# Display.net
KiCad netlist of a schematic drawn in Altium Designer
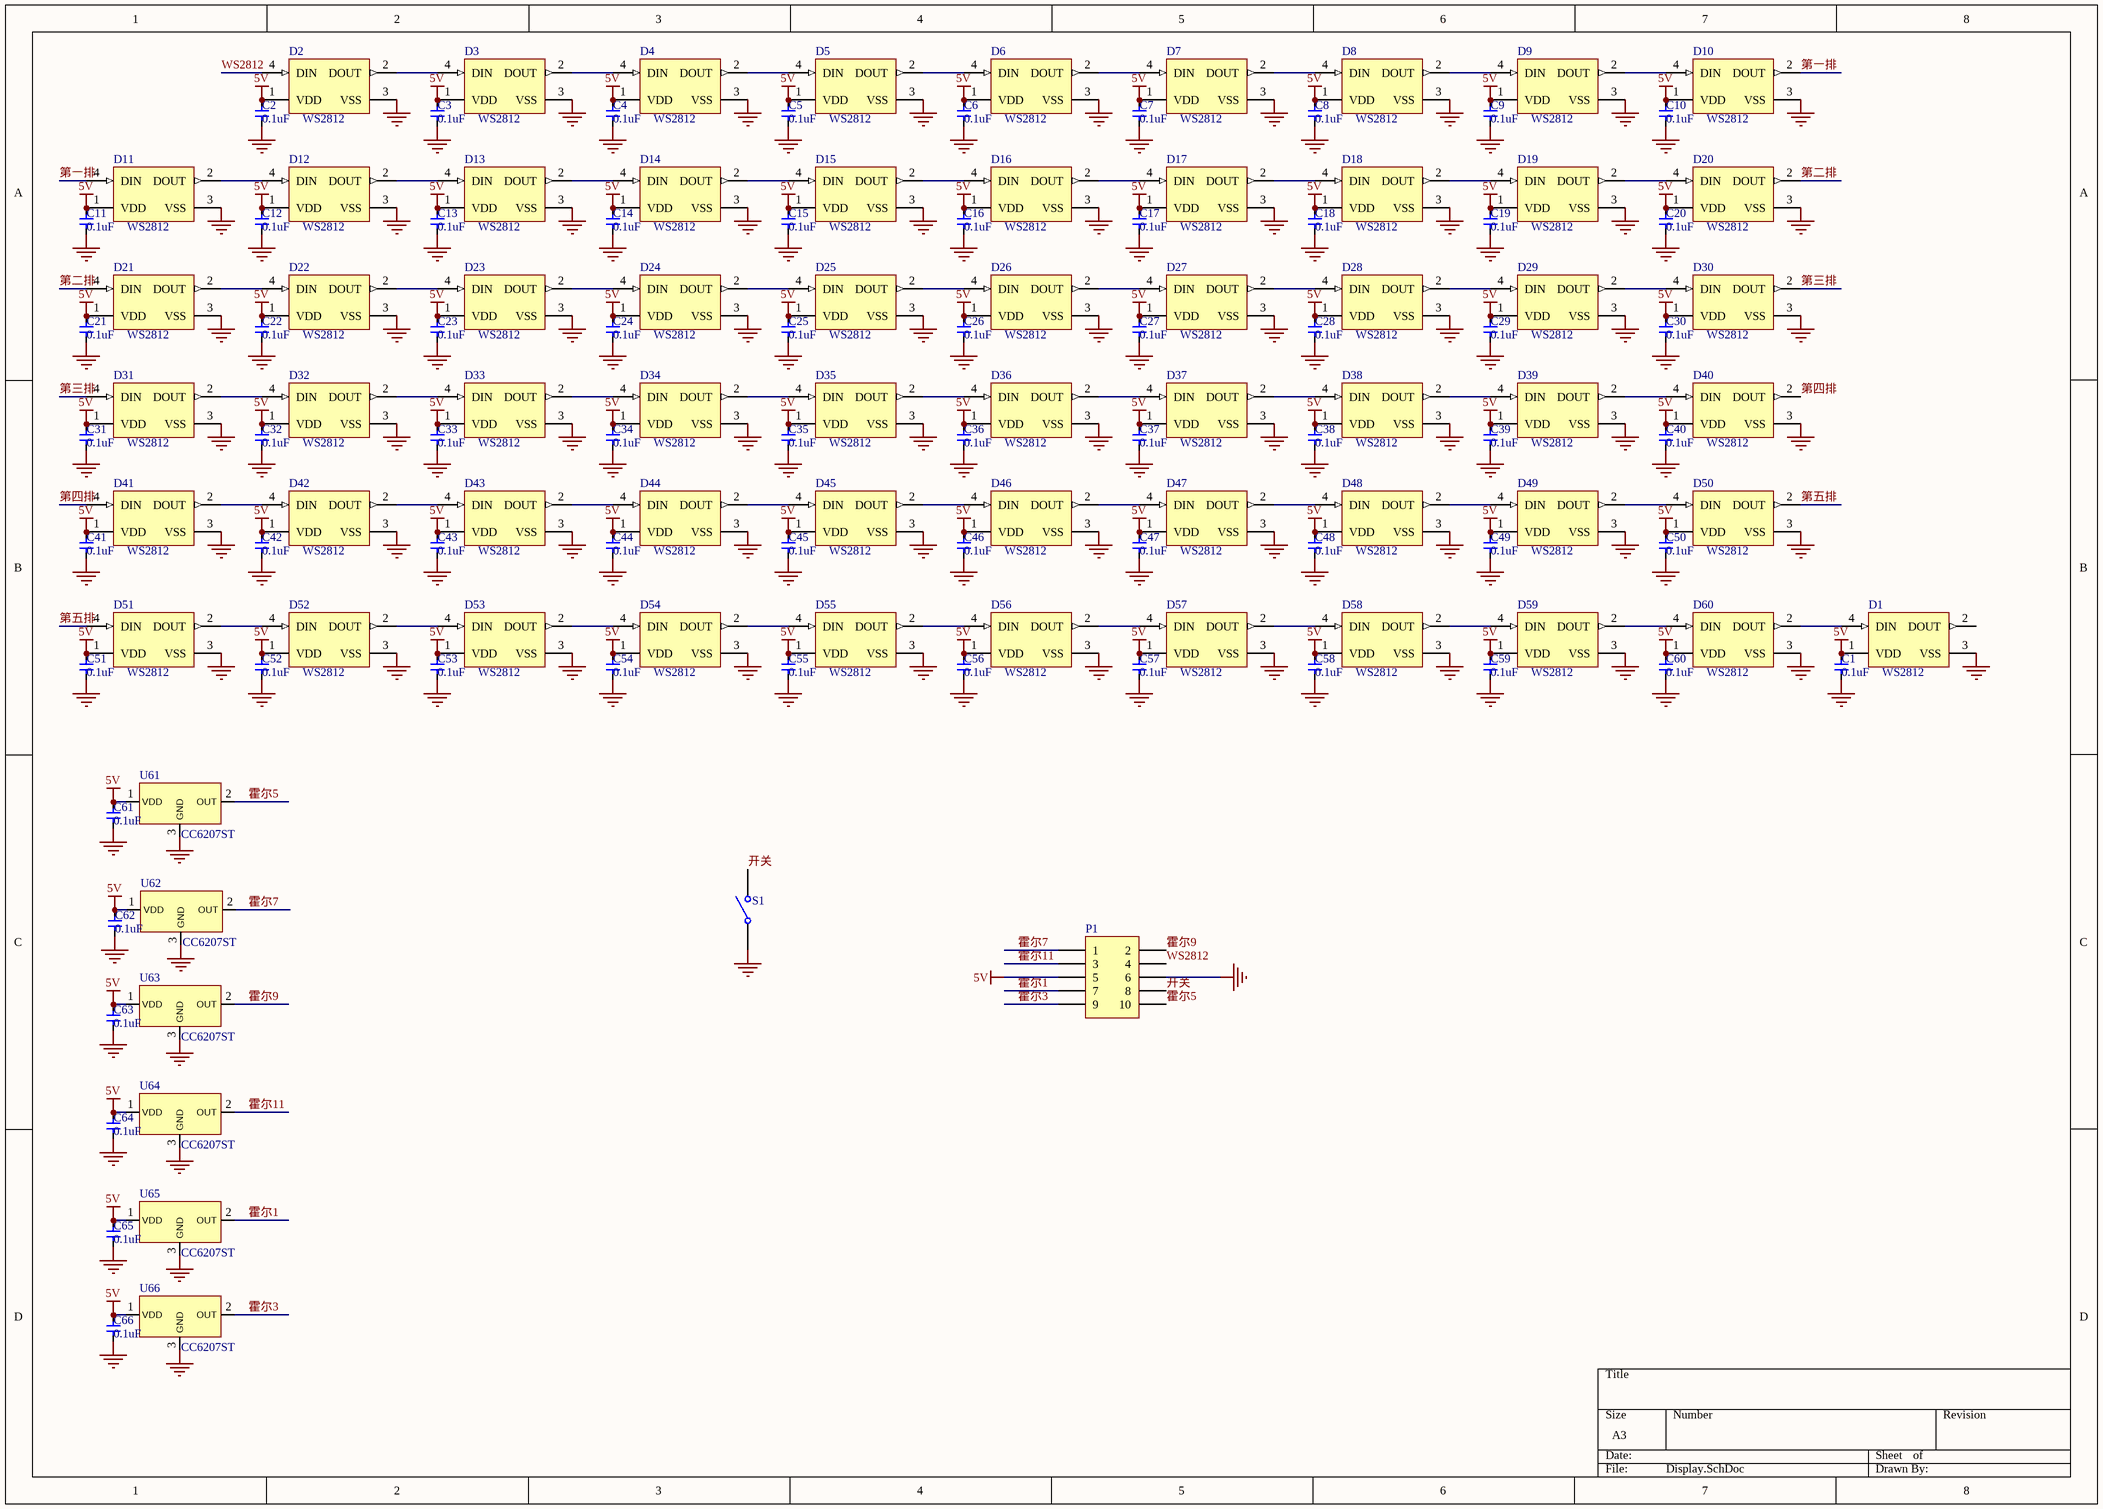
[diagram p0: Display.SchDoc]

(export (version "E")
  (design (tool "Eeschema 10.0.6"))
  (components
    (comp (ref "C1")
      (value "0.1uF")
      (footprint "0603_C")
      (description "Capacitor")
      (libsource (lib "MyPcbLib") (part "电容-0402"))
    )
    (comp (ref "C2")
      (value "0.1uF")
      (footprint "0603_C")
      (description "Capacitor")
      (libsource (lib "MyPcbLib") (part "电容-0402"))
    )
    (comp (ref "C3")
      (value "0.1uF")
      (footprint "0603_C")
      (description "Capacitor")
      (libsource (lib "MyPcbLib") (part "电容-0402"))
    )
    (comp (ref "C4")
      (value "0.1uF")
      (footprint "0603_C")
      (description "Capacitor")
      (libsource (lib "MyPcbLib") (part "电容-0402"))
    )
    (comp (ref "C5")
      (value "0.1uF")
      (footprint "0603_C")
      (description "Capacitor")
      (libsource (lib "MyPcbLib") (part "电容-0402"))
    )
    (comp (ref "C6")
      (value "0.1uF")
      (footprint "0603_C")
      (description "Capacitor")
      (libsource (lib "MyPcbLib") (part "电容-0402"))
    )
    (comp (ref "C7")
      (value "0.1uF")
      (footprint "0603_C")
      (description "Capacitor")
      (libsource (lib "MyPcbLib") (part "电容-0402"))
    )
    (comp (ref "C8")
      (value "0.1uF")
      (footprint "0603_C")
      (description "Capacitor")
      (libsource (lib "MyPcbLib") (part "电容-0402"))
    )
    (comp (ref "C9")
      (value "0.1uF")
      (footprint "0603_C")
      (description "Capacitor")
      (libsource (lib "MyPcbLib") (part "电容-0402"))
    )
    (comp (ref "C10")
      (value "0.1uF")
      (footprint "0603_C")
      (description "Capacitor")
      (libsource (lib "MyPcbLib") (part "电容-0402"))
    )
    (comp (ref "C11")
      (value "0.1uF")
      (footprint "0603_C")
      (description "Capacitor")
      (libsource (lib "MyPcbLib") (part "电容-0402"))
    )
    (comp (ref "C12")
      (value "0.1uF")
      (footprint "0603_C")
      (description "Capacitor")
      (libsource (lib "MyPcbLib") (part "电容-0402"))
    )
    (comp (ref "C13")
      (value "0.1uF")
      (footprint "0603_C")
      (description "Capacitor")
      (libsource (lib "MyPcbLib") (part "电容-0402"))
    )
    (comp (ref "C14")
      (value "0.1uF")
      (footprint "0603_C")
      (description "Capacitor")
      (libsource (lib "MyPcbLib") (part "电容-0402"))
    )
    (comp (ref "C15")
      (value "0.1uF")
      (footprint "0603_C")
      (description "Capacitor")
      (libsource (lib "MyPcbLib") (part "电容-0402"))
    )
    (comp (ref "C16")
      (value "0.1uF")
      (footprint "0603_C")
      (description "Capacitor")
      (libsource (lib "MyPcbLib") (part "电容-0402"))
    )
    (comp (ref "C17")
      (value "0.1uF")
      (footprint "0603_C")
      (description "Capacitor")
      (libsource (lib "MyPcbLib") (part "电容-0402"))
    )
    (comp (ref "C18")
      (value "0.1uF")
      (footprint "0603_C")
      (description "Capacitor")
      (libsource (lib "MyPcbLib") (part "电容-0402"))
    )
    (comp (ref "C19")
      (value "0.1uF")
      (footprint "0603_C")
      (description "Capacitor")
      (libsource (lib "MyPcbLib") (part "电容-0402"))
    )
    (comp (ref "C20")
      (value "0.1uF")
      (footprint "0603_C")
      (description "Capacitor")
      (libsource (lib "MyPcbLib") (part "电容-0402"))
    )
    (comp (ref "C21")
      (value "0.1uF")
      (footprint "0603_C")
      (description "Capacitor")
      (libsource (lib "MyPcbLib") (part "电容-0402"))
    )
    (comp (ref "C22")
      (value "0.1uF")
      (footprint "0603_C")
      (description "Capacitor")
      (libsource (lib "MyPcbLib") (part "电容-0402"))
    )
    (comp (ref "C23")
      (value "0.1uF")
      (footprint "0603_C")
      (description "Capacitor")
      (libsource (lib "MyPcbLib") (part "电容-0402"))
    )
    (comp (ref "C24")
      (value "0.1uF")
      (footprint "0603_C")
      (description "Capacitor")
      (libsource (lib "MyPcbLib") (part "电容-0402"))
    )
    (comp (ref "C25")
      (value "0.1uF")
      (footprint "0603_C")
      (description "Capacitor")
      (libsource (lib "MyPcbLib") (part "电容-0402"))
    )
    (comp (ref "C26")
      (value "0.1uF")
      (footprint "0603_C")
      (description "Capacitor")
      (libsource (lib "MyPcbLib") (part "电容-0402"))
    )
    (comp (ref "C27")
      (value "0.1uF")
      (footprint "0603_C")
      (description "Capacitor")
      (libsource (lib "MyPcbLib") (part "电容-0402"))
    )
    (comp (ref "C28")
      (value "0.1uF")
      (footprint "0603_C")
      (description "Capacitor")
      (libsource (lib "MyPcbLib") (part "电容-0402"))
    )
    (comp (ref "C29")
      (value "0.1uF")
      (footprint "0603_C")
      (description "Capacitor")
      (libsource (lib "MyPcbLib") (part "电容-0402"))
    )
    (comp (ref "C30")
      (value "0.1uF")
      (footprint "0603_C")
      (description "Capacitor")
      (libsource (lib "MyPcbLib") (part "电容-0402"))
    )
    (comp (ref "C31")
      (value "0.1uF")
      (footprint "0603_C")
      (description "Capacitor")
      (libsource (lib "MyPcbLib") (part "电容-0402"))
    )
    (comp (ref "C32")
      (value "0.1uF")
      (footprint "0603_C")
      (description "Capacitor")
      (libsource (lib "MyPcbLib") (part "电容-0402"))
    )
    (comp (ref "C33")
      (value "0.1uF")
      (footprint "0603_C")
      (description "Capacitor")
      (libsource (lib "MyPcbLib") (part "电容-0402"))
    )
    (comp (ref "C34")
      (value "0.1uF")
      (footprint "0603_C")
      (description "Capacitor")
      (libsource (lib "MyPcbLib") (part "电容-0402"))
    )
    (comp (ref "C35")
      (value "0.1uF")
      (footprint "0603_C")
      (description "Capacitor")
      (libsource (lib "MyPcbLib") (part "电容-0402"))
    )
    (comp (ref "C36")
      (value "0.1uF")
      (footprint "0603_C")
      (description "Capacitor")
      (libsource (lib "MyPcbLib") (part "电容-0402"))
    )
    (comp (ref "C37")
      (value "0.1uF")
      (footprint "0603_C")
      (description "Capacitor")
      (libsource (lib "MyPcbLib") (part "电容-0402"))
    )
    (comp (ref "C38")
      (value "0.1uF")
      (footprint "0603_C")
      (description "Capacitor")
      (libsource (lib "MyPcbLib") (part "电容-0402"))
    )
    (comp (ref "C39")
      (value "0.1uF")
      (footprint "0603_C")
      (description "Capacitor")
      (libsource (lib "MyPcbLib") (part "电容-0402"))
    )
    (comp (ref "C40")
      (value "0.1uF")
      (footprint "0603_C")
      (description "Capacitor")
      (libsource (lib "MyPcbLib") (part "电容-0402"))
    )
    (comp (ref "C41")
      (value "0.1uF")
      (footprint "0603_C")
      (description "Capacitor")
      (libsource (lib "MyPcbLib") (part "电容-0402"))
    )
    (comp (ref "C42")
      (value "0.1uF")
      (footprint "0603_C")
      (description "Capacitor")
      (libsource (lib "MyPcbLib") (part "电容-0402"))
    )
    (comp (ref "C43")
      (value "0.1uF")
      (footprint "0603_C")
      (description "Capacitor")
      (libsource (lib "MyPcbLib") (part "电容-0402"))
    )
    (comp (ref "C44")
      (value "0.1uF")
      (footprint "0603_C")
      (description "Capacitor")
      (libsource (lib "MyPcbLib") (part "电容-0402"))
    )
    (comp (ref "C45")
      (value "0.1uF")
      (footprint "0603_C")
      (description "Capacitor")
      (libsource (lib "MyPcbLib") (part "电容-0402"))
    )
    (comp (ref "C46")
      (value "0.1uF")
      (footprint "0603_C")
      (description "Capacitor")
      (libsource (lib "MyPcbLib") (part "电容-0402"))
    )
    (comp (ref "C47")
      (value "0.1uF")
      (footprint "0603_C")
      (description "Capacitor")
      (libsource (lib "MyPcbLib") (part "电容-0402"))
    )
    (comp (ref "C48")
      (value "0.1uF")
      (footprint "0603_C")
      (description "Capacitor")
      (libsource (lib "MyPcbLib") (part "电容-0402"))
    )
    (comp (ref "C49")
      (value "0.1uF")
      (footprint "0603_C")
      (description "Capacitor")
      (libsource (lib "MyPcbLib") (part "电容-0402"))
    )
    (comp (ref "C50")
      (value "0.1uF")
      (footprint "0603_C")
      (description "Capacitor")
      (libsource (lib "MyPcbLib") (part "电容-0402"))
    )
    (comp (ref "C51")
      (value "0.1uF")
      (footprint "0603_C")
      (description "Capacitor")
      (libsource (lib "MyPcbLib") (part "电容-0402"))
    )
    (comp (ref "C52")
      (value "0.1uF")
      (footprint "0603_C")
      (description "Capacitor")
      (libsource (lib "MyPcbLib") (part "电容-0402"))
    )
    (comp (ref "C53")
      (value "0.1uF")
      (footprint "0603_C")
      (description "Capacitor")
      (libsource (lib "MyPcbLib") (part "电容-0402"))
    )
    (comp (ref "C54")
      (value "0.1uF")
      (footprint "0603_C")
      (description "Capacitor")
      (libsource (lib "MyPcbLib") (part "电容-0402"))
    )
    (comp (ref "C55")
      (value "0.1uF")
      (footprint "0603_C")
      (description "Capacitor")
      (libsource (lib "MyPcbLib") (part "电容-0402"))
    )
    (comp (ref "C56")
      (value "0.1uF")
      (footprint "0603_C")
      (description "Capacitor")
      (libsource (lib "MyPcbLib") (part "电容-0402"))
    )
    (comp (ref "C57")
      (value "0.1uF")
      (footprint "0603_C")
      (description "Capacitor")
      (libsource (lib "MyPcbLib") (part "电容-0402"))
    )
    (comp (ref "C58")
      (value "0.1uF")
      (footprint "0603_C")
      (description "Capacitor")
      (libsource (lib "MyPcbLib") (part "电容-0402"))
    )
    (comp (ref "C59")
      (value "0.1uF")
      (footprint "0603_C")
      (description "Capacitor")
      (libsource (lib "MyPcbLib") (part "电容-0402"))
    )
    (comp (ref "C60")
      (value "0.1uF")
      (footprint "0603_C")
      (description "Capacitor")
      (libsource (lib "MyPcbLib") (part "电容-0402"))
    )
    (comp (ref "C61")
      (value "0.1uF")
      (footprint "0603_C")
      (description "Capacitor")
      (libsource (lib "MyPcbLib") (part "电容-0402"))
    )
    (comp (ref "C62")
      (value "0.1uF")
      (footprint "0603_C")
      (description "Capacitor")
      (libsource (lib "MyPcbLib") (part "电容-0402"))
    )
    (comp (ref "C63")
      (value "0.1uF")
      (footprint "0603_C")
      (description "Capacitor")
      (libsource (lib "MyPcbLib") (part "电容-0402"))
    )
    (comp (ref "C64")
      (value "0.1uF")
      (footprint "0603_C")
      (description "Capacitor")
      (libsource (lib "MyPcbLib") (part "电容-0402"))
    )
    (comp (ref "C65")
      (value "0.1uF")
      (footprint "0603_C")
      (description "Capacitor")
      (libsource (lib "MyPcbLib") (part "电容-0402"))
    )
    (comp (ref "C66")
      (value "0.1uF")
      (footprint "0603_C")
      (description "Capacitor")
      (libsource (lib "MyPcbLib") (part "电容-0402"))
    )
    (comp (ref "D1")
      (value "WS2812")
      (footprint "WS2812-2020")
      (fields (field (name "MANUFACTURER") "Adafruit-Industries-LLC"))
      (libsource (lib "SamacSys") (part "ADA-RGB-1655-4"))
    )
    (comp (ref "D2")
      (value "WS2812")
      (footprint "WS2812-2020")
      (fields (field (name "MANUFACTURER") "Adafruit-Industries-LLC"))
      (libsource (lib "SamacSys") (part "ADA-RGB-1655-4"))
    )
    (comp (ref "D3")
      (value "WS2812")
      (footprint "WS2812-2020")
      (fields (field (name "MANUFACTURER") "Adafruit-Industries-LLC"))
      (libsource (lib "SamacSys") (part "ADA-RGB-1655-4"))
    )
    (comp (ref "D4")
      (value "WS2812")
      (footprint "WS2812-2020")
      (fields (field (name "MANUFACTURER") "Adafruit-Industries-LLC"))
      (libsource (lib "SamacSys") (part "ADA-RGB-1655-4"))
    )
    (comp (ref "D5")
      (value "WS2812")
      (footprint "WS2812-2020")
      (fields (field (name "MANUFACTURER") "Adafruit-Industries-LLC"))
      (libsource (lib "SamacSys") (part "ADA-RGB-1655-4"))
    )
    (comp (ref "D6")
      (value "WS2812")
      (footprint "WS2812-2020")
      (fields (field (name "MANUFACTURER") "Adafruit-Industries-LLC"))
      (libsource (lib "SamacSys") (part "ADA-RGB-1655-4"))
    )
    (comp (ref "D7")
      (value "WS2812")
      (footprint "WS2812-2020")
      (fields (field (name "MANUFACTURER") "Adafruit-Industries-LLC"))
      (libsource (lib "SamacSys") (part "ADA-RGB-1655-4"))
    )
    (comp (ref "D8")
      (value "WS2812")
      (footprint "WS2812-2020")
      (fields (field (name "MANUFACTURER") "Adafruit-Industries-LLC"))
      (libsource (lib "SamacSys") (part "ADA-RGB-1655-4"))
    )
    (comp (ref "D9")
      (value "WS2812")
      (footprint "WS2812-2020")
      (fields (field (name "MANUFACTURER") "Adafruit-Industries-LLC"))
      (libsource (lib "SamacSys") (part "ADA-RGB-1655-4"))
    )
    (comp (ref "D10")
      (value "WS2812")
      (footprint "WS2812-2020")
      (fields (field (name "MANUFACTURER") "Adafruit-Industries-LLC"))
      (libsource (lib "SamacSys") (part "ADA-RGB-1655-4"))
    )
    (comp (ref "D11")
      (value "WS2812")
      (footprint "WS2812-2020")
      (fields (field (name "MANUFACTURER") "Adafruit-Industries-LLC"))
      (libsource (lib "SamacSys") (part "ADA-RGB-1655-4"))
    )
    (comp (ref "D12")
      (value "WS2812")
      (footprint "WS2812-2020")
      (fields (field (name "MANUFACTURER") "Adafruit-Industries-LLC"))
      (libsource (lib "SamacSys") (part "ADA-RGB-1655-4"))
    )
    (comp (ref "D13")
      (value "WS2812")
      (footprint "WS2812-2020")
      (fields (field (name "MANUFACTURER") "Adafruit-Industries-LLC"))
      (libsource (lib "SamacSys") (part "ADA-RGB-1655-4"))
    )
    (comp (ref "D14")
      (value "WS2812")
      (footprint "WS2812-2020")
      (fields (field (name "MANUFACTURER") "Adafruit-Industries-LLC"))
      (libsource (lib "SamacSys") (part "ADA-RGB-1655-4"))
    )
    (comp (ref "D15")
      (value "WS2812")
      (footprint "WS2812-2020")
      (fields (field (name "MANUFACTURER") "Adafruit-Industries-LLC"))
      (libsource (lib "SamacSys") (part "ADA-RGB-1655-4"))
    )
    (comp (ref "D16")
      (value "WS2812")
      (footprint "WS2812-2020")
      (fields (field (name "MANUFACTURER") "Adafruit-Industries-LLC"))
      (libsource (lib "SamacSys") (part "ADA-RGB-1655-4"))
    )
    (comp (ref "D17")
      (value "WS2812")
      (footprint "WS2812-2020")
      (fields (field (name "MANUFACTURER") "Adafruit-Industries-LLC"))
      (libsource (lib "SamacSys") (part "ADA-RGB-1655-4"))
    )
    (comp (ref "D18")
      (value "WS2812")
      (footprint "WS2812-2020")
      (fields (field (name "MANUFACTURER") "Adafruit-Industries-LLC"))
      (libsource (lib "SamacSys") (part "ADA-RGB-1655-4"))
    )
    (comp (ref "D19")
      (value "WS2812")
      (footprint "WS2812-2020")
      (fields (field (name "MANUFACTURER") "Adafruit-Industries-LLC"))
      (libsource (lib "SamacSys") (part "ADA-RGB-1655-4"))
    )
    (comp (ref "D20")
      (value "WS2812")
      (footprint "WS2812-2020")
      (fields (field (name "MANUFACTURER") "Adafruit-Industries-LLC"))
      (libsource (lib "SamacSys") (part "ADA-RGB-1655-4"))
    )
    (comp (ref "D21")
      (value "WS2812")
      (footprint "WS2812-2020")
      (fields (field (name "MANUFACTURER") "Adafruit-Industries-LLC"))
      (libsource (lib "SamacSys") (part "ADA-RGB-1655-4"))
    )
    (comp (ref "D22")
      (value "WS2812")
      (footprint "WS2812-2020")
      (fields (field (name "MANUFACTURER") "Adafruit-Industries-LLC"))
      (libsource (lib "SamacSys") (part "ADA-RGB-1655-4"))
    )
    (comp (ref "D23")
      (value "WS2812")
      (footprint "WS2812-2020")
      (fields (field (name "MANUFACTURER") "Adafruit-Industries-LLC"))
      (libsource (lib "SamacSys") (part "ADA-RGB-1655-4"))
    )
    (comp (ref "D24")
      (value "WS2812")
      (footprint "WS2812-2020")
      (fields (field (name "MANUFACTURER") "Adafruit-Industries-LLC"))
      (libsource (lib "SamacSys") (part "ADA-RGB-1655-4"))
    )
    (comp (ref "D25")
      (value "WS2812")
      (footprint "WS2812-2020")
      (fields (field (name "MANUFACTURER") "Adafruit-Industries-LLC"))
      (libsource (lib "SamacSys") (part "ADA-RGB-1655-4"))
    )
    (comp (ref "D26")
      (value "WS2812")
      (footprint "WS2812-2020")
      (fields (field (name "MANUFACTURER") "Adafruit-Industries-LLC"))
      (libsource (lib "SamacSys") (part "ADA-RGB-1655-4"))
    )
    (comp (ref "D27")
      (value "WS2812")
      (footprint "WS2812-2020")
      (fields (field (name "MANUFACTURER") "Adafruit-Industries-LLC"))
      (libsource (lib "SamacSys") (part "ADA-RGB-1655-4"))
    )
    (comp (ref "D28")
      (value "WS2812")
      (footprint "WS2812-2020")
      (fields (field (name "MANUFACTURER") "Adafruit-Industries-LLC"))
      (libsource (lib "SamacSys") (part "ADA-RGB-1655-4"))
    )
    (comp (ref "D29")
      (value "WS2812")
      (footprint "WS2812-2020")
      (fields (field (name "MANUFACTURER") "Adafruit-Industries-LLC"))
      (libsource (lib "SamacSys") (part "ADA-RGB-1655-4"))
    )
    (comp (ref "D30")
      (value "WS2812")
      (footprint "WS2812-2020")
      (fields (field (name "MANUFACTURER") "Adafruit-Industries-LLC"))
      (libsource (lib "SamacSys") (part "ADA-RGB-1655-4"))
    )
    (comp (ref "D31")
      (value "WS2812")
      (footprint "WS2812-2020")
      (fields (field (name "MANUFACTURER") "Adafruit-Industries-LLC"))
      (libsource (lib "SamacSys") (part "ADA-RGB-1655-4"))
    )
    (comp (ref "D32")
      (value "WS2812")
      (footprint "WS2812-2020")
      (fields (field (name "MANUFACTURER") "Adafruit-Industries-LLC"))
      (libsource (lib "SamacSys") (part "ADA-RGB-1655-4"))
    )
    (comp (ref "D33")
      (value "WS2812")
      (footprint "WS2812-2020")
      (fields (field (name "MANUFACTURER") "Adafruit-Industries-LLC"))
      (libsource (lib "SamacSys") (part "ADA-RGB-1655-4"))
    )
    (comp (ref "D34")
      (value "WS2812")
      (footprint "WS2812-2020")
      (fields (field (name "MANUFACTURER") "Adafruit-Industries-LLC"))
      (libsource (lib "SamacSys") (part "ADA-RGB-1655-4"))
    )
    (comp (ref "D35")
      (value "WS2812")
      (footprint "WS2812-2020")
      (fields (field (name "MANUFACTURER") "Adafruit-Industries-LLC"))
      (libsource (lib "SamacSys") (part "ADA-RGB-1655-4"))
    )
    (comp (ref "D36")
      (value "WS2812")
      (footprint "WS2812-2020")
      (fields (field (name "MANUFACTURER") "Adafruit-Industries-LLC"))
      (libsource (lib "SamacSys") (part "ADA-RGB-1655-4"))
    )
    (comp (ref "D37")
      (value "WS2812")
      (footprint "WS2812-2020")
      (fields (field (name "MANUFACTURER") "Adafruit-Industries-LLC"))
      (libsource (lib "SamacSys") (part "ADA-RGB-1655-4"))
    )
    (comp (ref "D38")
      (value "WS2812")
      (footprint "WS2812-2020")
      (fields (field (name "MANUFACTURER") "Adafruit-Industries-LLC"))
      (libsource (lib "SamacSys") (part "ADA-RGB-1655-4"))
    )
    (comp (ref "D39")
      (value "WS2812")
      (footprint "WS2812-2020")
      (fields (field (name "MANUFACTURER") "Adafruit-Industries-LLC"))
      (libsource (lib "SamacSys") (part "ADA-RGB-1655-4"))
    )
    (comp (ref "D40")
      (value "WS2812")
      (footprint "WS2812-2020")
      (fields (field (name "MANUFACTURER") "Adafruit-Industries-LLC"))
      (libsource (lib "SamacSys") (part "ADA-RGB-1655-4"))
    )
    (comp (ref "D41")
      (value "WS2812")
      (footprint "WS2812-2020")
      (fields (field (name "MANUFACTURER") "Adafruit-Industries-LLC"))
      (libsource (lib "SamacSys") (part "ADA-RGB-1655-4"))
    )
    (comp (ref "D42")
      (value "WS2812")
      (footprint "WS2812-2020")
      (fields (field (name "MANUFACTURER") "Adafruit-Industries-LLC"))
      (libsource (lib "SamacSys") (part "ADA-RGB-1655-4"))
    )
    (comp (ref "D43")
      (value "WS2812")
      (footprint "WS2812-2020")
      (fields (field (name "MANUFACTURER") "Adafruit-Industries-LLC"))
      (libsource (lib "SamacSys") (part "ADA-RGB-1655-4"))
    )
    (comp (ref "D44")
      (value "WS2812")
      (footprint "WS2812-2020")
      (fields (field (name "MANUFACTURER") "Adafruit-Industries-LLC"))
      (libsource (lib "SamacSys") (part "ADA-RGB-1655-4"))
    )
    (comp (ref "D45")
      (value "WS2812")
      (footprint "WS2812-2020")
      (fields (field (name "MANUFACTURER") "Adafruit-Industries-LLC"))
      (libsource (lib "SamacSys") (part "ADA-RGB-1655-4"))
    )
    (comp (ref "D46")
      (value "WS2812")
      (footprint "WS2812-2020")
      (fields (field (name "MANUFACTURER") "Adafruit-Industries-LLC"))
      (libsource (lib "SamacSys") (part "ADA-RGB-1655-4"))
    )
    (comp (ref "D47")
      (value "WS2812")
      (footprint "WS2812-2020")
      (fields (field (name "MANUFACTURER") "Adafruit-Industries-LLC"))
      (libsource (lib "SamacSys") (part "ADA-RGB-1655-4"))
    )
    (comp (ref "D48")
      (value "WS2812")
      (footprint "WS2812-2020")
      (fields (field (name "MANUFACTURER") "Adafruit-Industries-LLC"))
      (libsource (lib "SamacSys") (part "ADA-RGB-1655-4"))
    )
    (comp (ref "D49")
      (value "WS2812")
      (footprint "WS2812-2020")
      (fields (field (name "MANUFACTURER") "Adafruit-Industries-LLC"))
      (libsource (lib "SamacSys") (part "ADA-RGB-1655-4"))
    )
    (comp (ref "D50")
      (value "WS2812")
      (footprint "WS2812-2020")
      (fields (field (name "MANUFACTURER") "Adafruit-Industries-LLC"))
      (libsource (lib "SamacSys") (part "ADA-RGB-1655-4"))
    )
    (comp (ref "D51")
      (value "WS2812")
      (footprint "WS2812-2020")
      (fields (field (name "MANUFACTURER") "Adafruit-Industries-LLC"))
      (libsource (lib "SamacSys") (part "ADA-RGB-1655-4"))
    )
    (comp (ref "D52")
      (value "WS2812")
      (footprint "WS2812-2020")
      (fields (field (name "MANUFACTURER") "Adafruit-Industries-LLC"))
      (libsource (lib "SamacSys") (part "ADA-RGB-1655-4"))
    )
    (comp (ref "D53")
      (value "WS2812")
      (footprint "WS2812-2020")
      (fields (field (name "MANUFACTURER") "Adafruit-Industries-LLC"))
      (libsource (lib "SamacSys") (part "ADA-RGB-1655-4"))
    )
    (comp (ref "D54")
      (value "WS2812")
      (footprint "WS2812-2020")
      (fields (field (name "MANUFACTURER") "Adafruit-Industries-LLC"))
      (libsource (lib "SamacSys") (part "ADA-RGB-1655-4"))
    )
    (comp (ref "D55")
      (value "WS2812")
      (footprint "WS2812-2020")
      (fields (field (name "MANUFACTURER") "Adafruit-Industries-LLC"))
      (libsource (lib "SamacSys") (part "ADA-RGB-1655-4"))
    )
    (comp (ref "D56")
      (value "WS2812")
      (footprint "WS2812-2020")
      (fields (field (name "MANUFACTURER") "Adafruit-Industries-LLC"))
      (libsource (lib "SamacSys") (part "ADA-RGB-1655-4"))
    )
    (comp (ref "D57")
      (value "WS2812")
      (footprint "WS2812-2020")
      (fields (field (name "MANUFACTURER") "Adafruit-Industries-LLC"))
      (libsource (lib "SamacSys") (part "ADA-RGB-1655-4"))
    )
    (comp (ref "D58")
      (value "WS2812")
      (footprint "WS2812-2020")
      (fields (field (name "MANUFACTURER") "Adafruit-Industries-LLC"))
      (libsource (lib "SamacSys") (part "ADA-RGB-1655-4"))
    )
    (comp (ref "D59")
      (value "WS2812")
      (footprint "WS2812-2020")
      (fields (field (name "MANUFACTURER") "Adafruit-Industries-LLC"))
      (libsource (lib "SamacSys") (part "ADA-RGB-1655-4"))
    )
    (comp (ref "D60")
      (value "WS2812")
      (footprint "WS2812-2020")
      (fields (field (name "MANUFACTURER") "Adafruit-Industries-LLC"))
      (libsource (lib "SamacSys") (part "ADA-RGB-1655-4"))
    )
    (comp (ref "P1")
      (value "Header 5X2")
      (footprint "GoldFinger-2.54-5x2")
      (description "Header, 5-Pin, Dual row")
      (fields (field (name "PUBLISHER") "Altium Limited"))
      (libsource (lib "Miscellaneous Connectors") (part "Header 5X2"))
    )
    (comp (ref "S1")
      (value "SW-SPST")
      (footprint "contactor")
      (description "Single-Pole, Single-Throw Switch")
      (fields (field (name "PUBLISHER") "Altium Limited"))
      (libsource (lib "Miscellaneous Devices") (part "SW-SPST"))
    )
    (comp (ref "U61")
      (value "CC6207ST")
      (footprint "SOT23-3")
      (description "SOT-23 全极性锁存型微功耗霍尔效应开关传感器")
      (libsource (lib "BT-Speaker") (part "CC6207ST"))
    )
    (comp (ref "U62")
      (value "CC6207ST")
      (footprint "SOT23-3")
      (description "SOT-23 全极性锁存型微功耗霍尔效应开关传感器")
      (libsource (lib "BT-Speaker") (part "CC6207ST"))
    )
    (comp (ref "U63")
      (value "CC6207ST")
      (footprint "SOT23-3")
      (description "SOT-23 全极性锁存型微功耗霍尔效应开关传感器")
      (libsource (lib "BT-Speaker") (part "CC6207ST"))
    )
    (comp (ref "U64")
      (value "CC6207ST")
      (footprint "SOT23-3")
      (description "SOT-23 全极性锁存型微功耗霍尔效应开关传感器")
      (libsource (lib "BT-Speaker") (part "CC6207ST"))
    )
    (comp (ref "U65")
      (value "CC6207ST")
      (footprint "SOT23-3")
      (description "SOT-23 全极性锁存型微功耗霍尔效应开关传感器")
      (libsource (lib "BT-Speaker") (part "CC6207ST"))
    )
    (comp (ref "U66")
      (value "CC6207ST")
      (footprint "SOT23-3")
      (description "SOT-23 全极性锁存型微功耗霍尔效应开关传感器")
      (libsource (lib "BT-Speaker") (part "CC6207ST"))
    )
  )
  (nets
    (net (code "1") (name "/WS2812") (class "Default")
      (node (ref "D2") (pin "4") (pinfunction "DIN_4") (pintype "input"))
      (node (ref "P1") (pin "4") (pinfunction "4_4") (pintype "passive"))
    )
    (net (code "2") (name "/开关") (class "Default")
      (node (ref "P1") (pin "8") (pinfunction "8_8") (pintype "passive"))
      (node (ref "S1") (pin "2") (pinfunction "NO_2") (pintype "passive"))
    )
    (net (code "3") (name "/第一排") (class "Default")
      (node (ref "D10") (pin "2") (pinfunction "DOUT_2") (pintype "output"))
      (node (ref "D11") (pin "4") (pinfunction "DIN_4") (pintype "input"))
    )
    (net (code "4") (name "/第三排") (class "Default")
      (node (ref "D30") (pin "2") (pinfunction "DOUT_2") (pintype "output"))
      (node (ref "D31") (pin "4") (pinfunction "DIN_4") (pintype "input"))
    )
    (net (code "5") (name "/第二排") (class "Default")
      (node (ref "D20") (pin "2") (pinfunction "DOUT_2") (pintype "output"))
      (node (ref "D21") (pin "4") (pinfunction "DIN_4") (pintype "input"))
    )
    (net (code "6") (name "/第五排") (class "Default")
      (node (ref "D50") (pin "2") (pinfunction "DOUT_2") (pintype "output"))
      (node (ref "D51") (pin "4") (pinfunction "DIN_4") (pintype "input"))
    )
    (net (code "7") (name "/第四排") (class "Default")
      (node (ref "D40") (pin "2") (pinfunction "DOUT_2") (pintype "output"))
      (node (ref "D41") (pin "4") (pinfunction "DIN_4") (pintype "input"))
    )
    (net (code "8") (name "/霍尔1") (class "Default")
      (node (ref "P1") (pin "7") (pinfunction "7_7") (pintype "passive"))
      (node (ref "U65") (pin "2") (pinfunction "OUT_2") (pintype "passive"))
    )
    (net (code "9") (name "/霍尔3") (class "Default")
      (node (ref "P1") (pin "9") (pinfunction "9_9") (pintype "passive"))
      (node (ref "U66") (pin "2") (pinfunction "OUT_2") (pintype "passive"))
    )
    (net (code "10") (name "/霍尔5") (class "Default")
      (node (ref "P1") (pin "10") (pinfunction "10_10") (pintype "passive"))
      (node (ref "U61") (pin "2") (pinfunction "OUT_2") (pintype "passive"))
    )
    (net (code "11") (name "/霍尔7") (class "Default")
      (node (ref "P1") (pin "1") (pinfunction "1_1") (pintype "passive"))
      (node (ref "U62") (pin "2") (pinfunction "OUT_2") (pintype "passive"))
    )
    (net (code "12") (name "/霍尔9") (class "Default")
      (node (ref "P1") (pin "2") (pinfunction "2_2") (pintype "passive"))
      (node (ref "U63") (pin "2") (pinfunction "OUT_2") (pintype "passive"))
    )
    (net (code "13") (name "/霍尔11") (class "Default")
      (node (ref "P1") (pin "3") (pinfunction "3_3") (pintype "passive"))
      (node (ref "U64") (pin "2") (pinfunction "OUT_2") (pintype "passive"))
    )
    (net (code "14") (name "5V") (class "Default")
      (node (ref "C1") (pin "2") (pinfunction "2_2") (pintype "passive"))
      (node (ref "C10") (pin "2") (pinfunction "2_2") (pintype "passive"))
      (node (ref "C11") (pin "2") (pinfunction "2_2") (pintype "passive"))
      (node (ref "C12") (pin "2") (pinfunction "2_2") (pintype "passive"))
      (node (ref "C13") (pin "2") (pinfunction "2_2") (pintype "passive"))
      (node (ref "C14") (pin "2") (pinfunction "2_2") (pintype "passive"))
      (node (ref "C15") (pin "2") (pinfunction "2_2") (pintype "passive"))
      (node (ref "C16") (pin "2") (pinfunction "2_2") (pintype "passive"))
      (node (ref "C17") (pin "2") (pinfunction "2_2") (pintype "passive"))
      (node (ref "C18") (pin "2") (pinfunction "2_2") (pintype "passive"))
      (node (ref "C19") (pin "2") (pinfunction "2_2") (pintype "passive"))
      (node (ref "C2") (pin "2") (pinfunction "2_2") (pintype "passive"))
      (node (ref "C20") (pin "2") (pinfunction "2_2") (pintype "passive"))
      (node (ref "C21") (pin "2") (pinfunction "2_2") (pintype "passive"))
      (node (ref "C22") (pin "2") (pinfunction "2_2") (pintype "passive"))
      (node (ref "C23") (pin "2") (pinfunction "2_2") (pintype "passive"))
      (node (ref "C24") (pin "2") (pinfunction "2_2") (pintype "passive"))
      (node (ref "C25") (pin "2") (pinfunction "2_2") (pintype "passive"))
      (node (ref "C26") (pin "2") (pinfunction "2_2") (pintype "passive"))
      (node (ref "C27") (pin "2") (pinfunction "2_2") (pintype "passive"))
      (node (ref "C28") (pin "2") (pinfunction "2_2") (pintype "passive"))
      (node (ref "C29") (pin "2") (pinfunction "2_2") (pintype "passive"))
      (node (ref "C3") (pin "2") (pinfunction "2_2") (pintype "passive"))
      (node (ref "C30") (pin "2") (pinfunction "2_2") (pintype "passive"))
      (node (ref "C31") (pin "2") (pinfunction "2_2") (pintype "passive"))
      (node (ref "C32") (pin "2") (pinfunction "2_2") (pintype "passive"))
      (node (ref "C33") (pin "2") (pinfunction "2_2") (pintype "passive"))
      (node (ref "C34") (pin "2") (pinfunction "2_2") (pintype "passive"))
      (node (ref "C35") (pin "2") (pinfunction "2_2") (pintype "passive"))
      (node (ref "C36") (pin "2") (pinfunction "2_2") (pintype "passive"))
      (node (ref "C37") (pin "2") (pinfunction "2_2") (pintype "passive"))
      (node (ref "C38") (pin "2") (pinfunction "2_2") (pintype "passive"))
      (node (ref "C39") (pin "2") (pinfunction "2_2") (pintype "passive"))
      (node (ref "C4") (pin "2") (pinfunction "2_2") (pintype "passive"))
      (node (ref "C40") (pin "2") (pinfunction "2_2") (pintype "passive"))
      (node (ref "C41") (pin "2") (pinfunction "2_2") (pintype "passive"))
      (node (ref "C42") (pin "2") (pinfunction "2_2") (pintype "passive"))
      (node (ref "C43") (pin "2") (pinfunction "2_2") (pintype "passive"))
      (node (ref "C44") (pin "2") (pinfunction "2_2") (pintype "passive"))
      (node (ref "C45") (pin "2") (pinfunction "2_2") (pintype "passive"))
      (node (ref "C46") (pin "2") (pinfunction "2_2") (pintype "passive"))
      (node (ref "C47") (pin "2") (pinfunction "2_2") (pintype "passive"))
      (node (ref "C48") (pin "2") (pinfunction "2_2") (pintype "passive"))
      (node (ref "C49") (pin "2") (pinfunction "2_2") (pintype "passive"))
      (node (ref "C5") (pin "2") (pinfunction "2_2") (pintype "passive"))
      (node (ref "C50") (pin "2") (pinfunction "2_2") (pintype "passive"))
      (node (ref "C51") (pin "2") (pinfunction "2_2") (pintype "passive"))
      (node (ref "C52") (pin "2") (pinfunction "2_2") (pintype "passive"))
      (node (ref "C53") (pin "2") (pinfunction "2_2") (pintype "passive"))
      (node (ref "C54") (pin "2") (pinfunction "2_2") (pintype "passive"))
      (node (ref "C55") (pin "2") (pinfunction "2_2") (pintype "passive"))
      (node (ref "C56") (pin "2") (pinfunction "2_2") (pintype "passive"))
      (node (ref "C57") (pin "2") (pinfunction "2_2") (pintype "passive"))
      (node (ref "C58") (pin "2") (pinfunction "2_2") (pintype "passive"))
      (node (ref "C59") (pin "2") (pinfunction "2_2") (pintype "passive"))
      (node (ref "C6") (pin "2") (pinfunction "2_2") (pintype "passive"))
      (node (ref "C60") (pin "2") (pinfunction "2_2") (pintype "passive"))
      (node (ref "C61") (pin "2") (pinfunction "2_2") (pintype "passive"))
      (node (ref "C62") (pin "2") (pinfunction "2_2") (pintype "passive"))
      (node (ref "C63") (pin "2") (pinfunction "2_2") (pintype "passive"))
      (node (ref "C64") (pin "2") (pinfunction "2_2") (pintype "passive"))
      (node (ref "C65") (pin "2") (pinfunction "2_2") (pintype "passive"))
      (node (ref "C66") (pin "2") (pinfunction "2_2") (pintype "passive"))
      (node (ref "C7") (pin "2") (pinfunction "2_2") (pintype "passive"))
      (node (ref "C8") (pin "2") (pinfunction "2_2") (pintype "passive"))
      (node (ref "C9") (pin "2") (pinfunction "2_2") (pintype "passive"))
      (node (ref "D1") (pin "1") (pinfunction "VDD_1") (pintype "power_in"))
      (node (ref "D10") (pin "1") (pinfunction "VDD_1") (pintype "power_in"))
      (node (ref "D11") (pin "1") (pinfunction "VDD_1") (pintype "power_in"))
      (node (ref "D12") (pin "1") (pinfunction "VDD_1") (pintype "power_in"))
      (node (ref "D13") (pin "1") (pinfunction "VDD_1") (pintype "power_in"))
      (node (ref "D14") (pin "1") (pinfunction "VDD_1") (pintype "power_in"))
      (node (ref "D15") (pin "1") (pinfunction "VDD_1") (pintype "power_in"))
      (node (ref "D16") (pin "1") (pinfunction "VDD_1") (pintype "power_in"))
      (node (ref "D17") (pin "1") (pinfunction "VDD_1") (pintype "power_in"))
      (node (ref "D18") (pin "1") (pinfunction "VDD_1") (pintype "power_in"))
      (node (ref "D19") (pin "1") (pinfunction "VDD_1") (pintype "power_in"))
      (node (ref "D2") (pin "1") (pinfunction "VDD_1") (pintype "power_in"))
      (node (ref "D20") (pin "1") (pinfunction "VDD_1") (pintype "power_in"))
      (node (ref "D21") (pin "1") (pinfunction "VDD_1") (pintype "power_in"))
      (node (ref "D22") (pin "1") (pinfunction "VDD_1") (pintype "power_in"))
      (node (ref "D23") (pin "1") (pinfunction "VDD_1") (pintype "power_in"))
      (node (ref "D24") (pin "1") (pinfunction "VDD_1") (pintype "power_in"))
      (node (ref "D25") (pin "1") (pinfunction "VDD_1") (pintype "power_in"))
      (node (ref "D26") (pin "1") (pinfunction "VDD_1") (pintype "power_in"))
      (node (ref "D27") (pin "1") (pinfunction "VDD_1") (pintype "power_in"))
      (node (ref "D28") (pin "1") (pinfunction "VDD_1") (pintype "power_in"))
      (node (ref "D29") (pin "1") (pinfunction "VDD_1") (pintype "power_in"))
      (node (ref "D3") (pin "1") (pinfunction "VDD_1") (pintype "power_in"))
      (node (ref "D30") (pin "1") (pinfunction "VDD_1") (pintype "power_in"))
      (node (ref "D31") (pin "1") (pinfunction "VDD_1") (pintype "power_in"))
      (node (ref "D32") (pin "1") (pinfunction "VDD_1") (pintype "power_in"))
      (node (ref "D33") (pin "1") (pinfunction "VDD_1") (pintype "power_in"))
      (node (ref "D34") (pin "1") (pinfunction "VDD_1") (pintype "power_in"))
      (node (ref "D35") (pin "1") (pinfunction "VDD_1") (pintype "power_in"))
      (node (ref "D36") (pin "1") (pinfunction "VDD_1") (pintype "power_in"))
      (node (ref "D37") (pin "1") (pinfunction "VDD_1") (pintype "power_in"))
      (node (ref "D38") (pin "1") (pinfunction "VDD_1") (pintype "power_in"))
      (node (ref "D39") (pin "1") (pinfunction "VDD_1") (pintype "power_in"))
      (node (ref "D4") (pin "1") (pinfunction "VDD_1") (pintype "power_in"))
      (node (ref "D40") (pin "1") (pinfunction "VDD_1") (pintype "power_in"))
      (node (ref "D41") (pin "1") (pinfunction "VDD_1") (pintype "power_in"))
      (node (ref "D42") (pin "1") (pinfunction "VDD_1") (pintype "power_in"))
      (node (ref "D43") (pin "1") (pinfunction "VDD_1") (pintype "power_in"))
      (node (ref "D44") (pin "1") (pinfunction "VDD_1") (pintype "power_in"))
      (node (ref "D45") (pin "1") (pinfunction "VDD_1") (pintype "power_in"))
      (node (ref "D46") (pin "1") (pinfunction "VDD_1") (pintype "power_in"))
      (node (ref "D47") (pin "1") (pinfunction "VDD_1") (pintype "power_in"))
      (node (ref "D48") (pin "1") (pinfunction "VDD_1") (pintype "power_in"))
      (node (ref "D49") (pin "1") (pinfunction "VDD_1") (pintype "power_in"))
      (node (ref "D5") (pin "1") (pinfunction "VDD_1") (pintype "power_in"))
      (node (ref "D50") (pin "1") (pinfunction "VDD_1") (pintype "power_in"))
      (node (ref "D51") (pin "1") (pinfunction "VDD_1") (pintype "power_in"))
      (node (ref "D52") (pin "1") (pinfunction "VDD_1") (pintype "power_in"))
      (node (ref "D53") (pin "1") (pinfunction "VDD_1") (pintype "power_in"))
      (node (ref "D54") (pin "1") (pinfunction "VDD_1") (pintype "power_in"))
      (node (ref "D55") (pin "1") (pinfunction "VDD_1") (pintype "power_in"))
      (node (ref "D56") (pin "1") (pinfunction "VDD_1") (pintype "power_in"))
      (node (ref "D57") (pin "1") (pinfunction "VDD_1") (pintype "power_in"))
      (node (ref "D58") (pin "1") (pinfunction "VDD_1") (pintype "power_in"))
      (node (ref "D59") (pin "1") (pinfunction "VDD_1") (pintype "power_in"))
      (node (ref "D6") (pin "1") (pinfunction "VDD_1") (pintype "power_in"))
      (node (ref "D60") (pin "1") (pinfunction "VDD_1") (pintype "power_in"))
      (node (ref "D7") (pin "1") (pinfunction "VDD_1") (pintype "power_in"))
      (node (ref "D8") (pin "1") (pinfunction "VDD_1") (pintype "power_in"))
      (node (ref "D9") (pin "1") (pinfunction "VDD_1") (pintype "power_in"))
      (node (ref "P1") (pin "5") (pinfunction "5_5") (pintype "passive"))
      (node (ref "U61") (pin "1") (pinfunction "VDD_1") (pintype "passive"))
      (node (ref "U62") (pin "1") (pinfunction "VDD_1") (pintype "passive"))
      (node (ref "U63") (pin "1") (pinfunction "VDD_1") (pintype "passive"))
      (node (ref "U64") (pin "1") (pinfunction "VDD_1") (pintype "passive"))
      (node (ref "U65") (pin "1") (pinfunction "VDD_1") (pintype "passive"))
      (node (ref "U66") (pin "1") (pinfunction "VDD_1") (pintype "passive"))
    )
    (net (code "15") (name "GND") (class "Default")
      (node (ref "C1") (pin "1") (pinfunction "1_1") (pintype "passive"))
      (node (ref "C10") (pin "1") (pinfunction "1_1") (pintype "passive"))
      (node (ref "C11") (pin "1") (pinfunction "1_1") (pintype "passive"))
      (node (ref "C12") (pin "1") (pinfunction "1_1") (pintype "passive"))
      (node (ref "C13") (pin "1") (pinfunction "1_1") (pintype "passive"))
      (node (ref "C14") (pin "1") (pinfunction "1_1") (pintype "passive"))
      (node (ref "C15") (pin "1") (pinfunction "1_1") (pintype "passive"))
      (node (ref "C16") (pin "1") (pinfunction "1_1") (pintype "passive"))
      (node (ref "C17") (pin "1") (pinfunction "1_1") (pintype "passive"))
      (node (ref "C18") (pin "1") (pinfunction "1_1") (pintype "passive"))
      (node (ref "C19") (pin "1") (pinfunction "1_1") (pintype "passive"))
      (node (ref "C2") (pin "1") (pinfunction "1_1") (pintype "passive"))
      (node (ref "C20") (pin "1") (pinfunction "1_1") (pintype "passive"))
      (node (ref "C21") (pin "1") (pinfunction "1_1") (pintype "passive"))
      (node (ref "C22") (pin "1") (pinfunction "1_1") (pintype "passive"))
      (node (ref "C23") (pin "1") (pinfunction "1_1") (pintype "passive"))
      (node (ref "C24") (pin "1") (pinfunction "1_1") (pintype "passive"))
      (node (ref "C25") (pin "1") (pinfunction "1_1") (pintype "passive"))
      (node (ref "C26") (pin "1") (pinfunction "1_1") (pintype "passive"))
      (node (ref "C27") (pin "1") (pinfunction "1_1") (pintype "passive"))
      (node (ref "C28") (pin "1") (pinfunction "1_1") (pintype "passive"))
      (node (ref "C29") (pin "1") (pinfunction "1_1") (pintype "passive"))
      (node (ref "C3") (pin "1") (pinfunction "1_1") (pintype "passive"))
      (node (ref "C30") (pin "1") (pinfunction "1_1") (pintype "passive"))
      (node (ref "C31") (pin "1") (pinfunction "1_1") (pintype "passive"))
      (node (ref "C32") (pin "1") (pinfunction "1_1") (pintype "passive"))
      (node (ref "C33") (pin "1") (pinfunction "1_1") (pintype "passive"))
      (node (ref "C34") (pin "1") (pinfunction "1_1") (pintype "passive"))
      (node (ref "C35") (pin "1") (pinfunction "1_1") (pintype "passive"))
      (node (ref "C36") (pin "1") (pinfunction "1_1") (pintype "passive"))
      (node (ref "C37") (pin "1") (pinfunction "1_1") (pintype "passive"))
      (node (ref "C38") (pin "1") (pinfunction "1_1") (pintype "passive"))
      (node (ref "C39") (pin "1") (pinfunction "1_1") (pintype "passive"))
      (node (ref "C4") (pin "1") (pinfunction "1_1") (pintype "passive"))
      (node (ref "C40") (pin "1") (pinfunction "1_1") (pintype "passive"))
      (node (ref "C41") (pin "1") (pinfunction "1_1") (pintype "passive"))
      (node (ref "C42") (pin "1") (pinfunction "1_1") (pintype "passive"))
      (node (ref "C43") (pin "1") (pinfunction "1_1") (pintype "passive"))
      (node (ref "C44") (pin "1") (pinfunction "1_1") (pintype "passive"))
      (node (ref "C45") (pin "1") (pinfunction "1_1") (pintype "passive"))
      (node (ref "C46") (pin "1") (pinfunction "1_1") (pintype "passive"))
      (node (ref "C47") (pin "1") (pinfunction "1_1") (pintype "passive"))
      (node (ref "C48") (pin "1") (pinfunction "1_1") (pintype "passive"))
      (node (ref "C49") (pin "1") (pinfunction "1_1") (pintype "passive"))
      (node (ref "C5") (pin "1") (pinfunction "1_1") (pintype "passive"))
      (node (ref "C50") (pin "1") (pinfunction "1_1") (pintype "passive"))
      (node (ref "C51") (pin "1") (pinfunction "1_1") (pintype "passive"))
      (node (ref "C52") (pin "1") (pinfunction "1_1") (pintype "passive"))
      (node (ref "C53") (pin "1") (pinfunction "1_1") (pintype "passive"))
      (node (ref "C54") (pin "1") (pinfunction "1_1") (pintype "passive"))
      (node (ref "C55") (pin "1") (pinfunction "1_1") (pintype "passive"))
      (node (ref "C56") (pin "1") (pinfunction "1_1") (pintype "passive"))
      (node (ref "C57") (pin "1") (pinfunction "1_1") (pintype "passive"))
      (node (ref "C58") (pin "1") (pinfunction "1_1") (pintype "passive"))
      (node (ref "C59") (pin "1") (pinfunction "1_1") (pintype "passive"))
      (node (ref "C6") (pin "1") (pinfunction "1_1") (pintype "passive"))
      (node (ref "C60") (pin "1") (pinfunction "1_1") (pintype "passive"))
      (node (ref "C61") (pin "1") (pinfunction "1_1") (pintype "passive"))
      (node (ref "C62") (pin "1") (pinfunction "1_1") (pintype "passive"))
      (node (ref "C63") (pin "1") (pinfunction "1_1") (pintype "passive"))
      (node (ref "C64") (pin "1") (pinfunction "1_1") (pintype "passive"))
      (node (ref "C65") (pin "1") (pinfunction "1_1") (pintype "passive"))
      (node (ref "C66") (pin "1") (pinfunction "1_1") (pintype "passive"))
      (node (ref "C7") (pin "1") (pinfunction "1_1") (pintype "passive"))
      (node (ref "C8") (pin "1") (pinfunction "1_1") (pintype "passive"))
      (node (ref "C9") (pin "1") (pinfunction "1_1") (pintype "passive"))
      (node (ref "D1") (pin "3") (pinfunction "VSS_3") (pintype "power_in"))
      (node (ref "D10") (pin "3") (pinfunction "VSS_3") (pintype "power_in"))
      (node (ref "D11") (pin "3") (pinfunction "VSS_3") (pintype "power_in"))
      (node (ref "D12") (pin "3") (pinfunction "VSS_3") (pintype "power_in"))
      (node (ref "D13") (pin "3") (pinfunction "VSS_3") (pintype "power_in"))
      (node (ref "D14") (pin "3") (pinfunction "VSS_3") (pintype "power_in"))
      (node (ref "D15") (pin "3") (pinfunction "VSS_3") (pintype "power_in"))
      (node (ref "D16") (pin "3") (pinfunction "VSS_3") (pintype "power_in"))
      (node (ref "D17") (pin "3") (pinfunction "VSS_3") (pintype "power_in"))
      (node (ref "D18") (pin "3") (pinfunction "VSS_3") (pintype "power_in"))
      (node (ref "D19") (pin "3") (pinfunction "VSS_3") (pintype "power_in"))
      (node (ref "D2") (pin "3") (pinfunction "VSS_3") (pintype "power_in"))
      (node (ref "D20") (pin "3") (pinfunction "VSS_3") (pintype "power_in"))
      (node (ref "D21") (pin "3") (pinfunction "VSS_3") (pintype "power_in"))
      (node (ref "D22") (pin "3") (pinfunction "VSS_3") (pintype "power_in"))
      (node (ref "D23") (pin "3") (pinfunction "VSS_3") (pintype "power_in"))
      (node (ref "D24") (pin "3") (pinfunction "VSS_3") (pintype "power_in"))
      (node (ref "D25") (pin "3") (pinfunction "VSS_3") (pintype "power_in"))
      (node (ref "D26") (pin "3") (pinfunction "VSS_3") (pintype "power_in"))
      (node (ref "D27") (pin "3") (pinfunction "VSS_3") (pintype "power_in"))
      (node (ref "D28") (pin "3") (pinfunction "VSS_3") (pintype "power_in"))
      (node (ref "D29") (pin "3") (pinfunction "VSS_3") (pintype "power_in"))
      (node (ref "D3") (pin "3") (pinfunction "VSS_3") (pintype "power_in"))
      (node (ref "D30") (pin "3") (pinfunction "VSS_3") (pintype "power_in"))
      (node (ref "D31") (pin "3") (pinfunction "VSS_3") (pintype "power_in"))
      (node (ref "D32") (pin "3") (pinfunction "VSS_3") (pintype "power_in"))
      (node (ref "D33") (pin "3") (pinfunction "VSS_3") (pintype "power_in"))
      (node (ref "D34") (pin "3") (pinfunction "VSS_3") (pintype "power_in"))
      (node (ref "D35") (pin "3") (pinfunction "VSS_3") (pintype "power_in"))
      (node (ref "D36") (pin "3") (pinfunction "VSS_3") (pintype "power_in"))
      (node (ref "D37") (pin "3") (pinfunction "VSS_3") (pintype "power_in"))
      (node (ref "D38") (pin "3") (pinfunction "VSS_3") (pintype "power_in"))
      (node (ref "D39") (pin "3") (pinfunction "VSS_3") (pintype "power_in"))
      (node (ref "D4") (pin "3") (pinfunction "VSS_3") (pintype "power_in"))
      (node (ref "D40") (pin "3") (pinfunction "VSS_3") (pintype "power_in"))
      (node (ref "D41") (pin "3") (pinfunction "VSS_3") (pintype "power_in"))
      (node (ref "D42") (pin "3") (pinfunction "VSS_3") (pintype "power_in"))
      (node (ref "D43") (pin "3") (pinfunction "VSS_3") (pintype "power_in"))
      (node (ref "D44") (pin "3") (pinfunction "VSS_3") (pintype "power_in"))
      (node (ref "D45") (pin "3") (pinfunction "VSS_3") (pintype "power_in"))
      (node (ref "D46") (pin "3") (pinfunction "VSS_3") (pintype "power_in"))
      (node (ref "D47") (pin "3") (pinfunction "VSS_3") (pintype "power_in"))
      (node (ref "D48") (pin "3") (pinfunction "VSS_3") (pintype "power_in"))
      (node (ref "D49") (pin "3") (pinfunction "VSS_3") (pintype "power_in"))
      (node (ref "D5") (pin "3") (pinfunction "VSS_3") (pintype "power_in"))
      (node (ref "D50") (pin "3") (pinfunction "VSS_3") (pintype "power_in"))
      (node (ref "D51") (pin "3") (pinfunction "VSS_3") (pintype "power_in"))
      (node (ref "D52") (pin "3") (pinfunction "VSS_3") (pintype "power_in"))
      (node (ref "D53") (pin "3") (pinfunction "VSS_3") (pintype "power_in"))
      (node (ref "D54") (pin "3") (pinfunction "VSS_3") (pintype "power_in"))
      (node (ref "D55") (pin "3") (pinfunction "VSS_3") (pintype "power_in"))
      (node (ref "D56") (pin "3") (pinfunction "VSS_3") (pintype "power_in"))
      (node (ref "D57") (pin "3") (pinfunction "VSS_3") (pintype "power_in"))
      (node (ref "D58") (pin "3") (pinfunction "VSS_3") (pintype "power_in"))
      (node (ref "D59") (pin "3") (pinfunction "VSS_3") (pintype "power_in"))
      (node (ref "D6") (pin "3") (pinfunction "VSS_3") (pintype "power_in"))
      (node (ref "D60") (pin "3") (pinfunction "VSS_3") (pintype "power_in"))
      (node (ref "D7") (pin "3") (pinfunction "VSS_3") (pintype "power_in"))
      (node (ref "D8") (pin "3") (pinfunction "VSS_3") (pintype "power_in"))
      (node (ref "D9") (pin "3") (pinfunction "VSS_3") (pintype "power_in"))
      (node (ref "P1") (pin "6") (pinfunction "6_6") (pintype "passive"))
      (node (ref "S1") (pin "1") (pinfunction "COMMON_1") (pintype "passive"))
      (node (ref "U61") (pin "3") (pinfunction "GND_3") (pintype "passive"))
      (node (ref "U62") (pin "3") (pinfunction "GND_3") (pintype "passive"))
      (node (ref "U63") (pin "3") (pinfunction "GND_3") (pintype "passive"))
      (node (ref "U64") (pin "3") (pinfunction "GND_3") (pintype "passive"))
      (node (ref "U65") (pin "3") (pinfunction "GND_3") (pintype "passive"))
      (node (ref "U66") (pin "3") (pinfunction "GND_3") (pintype "passive"))
    )
    (net (code "16") (name "Net-(D1-DIN)") (class "Default")
      (node (ref "D1") (pin "4") (pinfunction "DIN_4") (pintype "input"))
      (node (ref "D60") (pin "2") (pinfunction "DOUT_2") (pintype "output"))
    )
    (net (code "17") (name "Net-(D2-DOUT)") (class "Default")
      (node (ref "D2") (pin "2") (pinfunction "DOUT_2") (pintype "output"))
      (node (ref "D3") (pin "4") (pinfunction "DIN_4") (pintype "input"))
    )
    (net (code "18") (name "Net-(D3-DOUT)") (class "Default")
      (node (ref "D3") (pin "2") (pinfunction "DOUT_2") (pintype "output"))
      (node (ref "D4") (pin "4") (pinfunction "DIN_4") (pintype "input"))
    )
    (net (code "19") (name "Net-(D4-DOUT)") (class "Default")
      (node (ref "D4") (pin "2") (pinfunction "DOUT_2") (pintype "output"))
      (node (ref "D5") (pin "4") (pinfunction "DIN_4") (pintype "input"))
    )
    (net (code "20") (name "Net-(D5-DOUT)") (class "Default")
      (node (ref "D5") (pin "2") (pinfunction "DOUT_2") (pintype "output"))
      (node (ref "D6") (pin "4") (pinfunction "DIN_4") (pintype "input"))
    )
    (net (code "21") (name "Net-(D6-DOUT)") (class "Default")
      (node (ref "D6") (pin "2") (pinfunction "DOUT_2") (pintype "output"))
      (node (ref "D7") (pin "4") (pinfunction "DIN_4") (pintype "input"))
    )
    (net (code "22") (name "Net-(D7-DOUT)") (class "Default")
      (node (ref "D7") (pin "2") (pinfunction "DOUT_2") (pintype "output"))
      (node (ref "D8") (pin "4") (pinfunction "DIN_4") (pintype "input"))
    )
    (net (code "23") (name "Net-(D8-DOUT)") (class "Default")
      (node (ref "D8") (pin "2") (pinfunction "DOUT_2") (pintype "output"))
      (node (ref "D9") (pin "4") (pinfunction "DIN_4") (pintype "input"))
    )
    (net (code "24") (name "Net-(D10-DIN)") (class "Default")
      (node (ref "D10") (pin "4") (pinfunction "DIN_4") (pintype "input"))
      (node (ref "D9") (pin "2") (pinfunction "DOUT_2") (pintype "output"))
    )
    (net (code "25") (name "Net-(D11-DOUT)") (class "Default")
      (node (ref "D11") (pin "2") (pinfunction "DOUT_2") (pintype "output"))
      (node (ref "D12") (pin "4") (pinfunction "DIN_4") (pintype "input"))
    )
    (net (code "26") (name "Net-(D12-DOUT)") (class "Default")
      (node (ref "D12") (pin "2") (pinfunction "DOUT_2") (pintype "output"))
      (node (ref "D13") (pin "4") (pinfunction "DIN_4") (pintype "input"))
    )
    (net (code "27") (name "Net-(D13-DOUT)") (class "Default")
      (node (ref "D13") (pin "2") (pinfunction "DOUT_2") (pintype "output"))
      (node (ref "D14") (pin "4") (pinfunction "DIN_4") (pintype "input"))
    )
    (net (code "28") (name "Net-(D14-DOUT)") (class "Default")
      (node (ref "D14") (pin "2") (pinfunction "DOUT_2") (pintype "output"))
      (node (ref "D15") (pin "4") (pinfunction "DIN_4") (pintype "input"))
    )
    (net (code "29") (name "Net-(D15-DOUT)") (class "Default")
      (node (ref "D15") (pin "2") (pinfunction "DOUT_2") (pintype "output"))
      (node (ref "D16") (pin "4") (pinfunction "DIN_4") (pintype "input"))
    )
    (net (code "30") (name "Net-(D16-DOUT)") (class "Default")
      (node (ref "D16") (pin "2") (pinfunction "DOUT_2") (pintype "output"))
      (node (ref "D17") (pin "4") (pinfunction "DIN_4") (pintype "input"))
    )
    (net (code "31") (name "Net-(D17-DOUT)") (class "Default")
      (node (ref "D17") (pin "2") (pinfunction "DOUT_2") (pintype "output"))
      (node (ref "D18") (pin "4") (pinfunction "DIN_4") (pintype "input"))
    )
    (net (code "32") (name "Net-(D18-DOUT)") (class "Default")
      (node (ref "D18") (pin "2") (pinfunction "DOUT_2") (pintype "output"))
      (node (ref "D19") (pin "4") (pinfunction "DIN_4") (pintype "input"))
    )
    (net (code "33") (name "Net-(D19-DOUT)") (class "Default")
      (node (ref "D19") (pin "2") (pinfunction "DOUT_2") (pintype "output"))
      (node (ref "D20") (pin "4") (pinfunction "DIN_4") (pintype "input"))
    )
    (net (code "34") (name "Net-(D21-DOUT)") (class "Default")
      (node (ref "D21") (pin "2") (pinfunction "DOUT_2") (pintype "output"))
      (node (ref "D22") (pin "4") (pinfunction "DIN_4") (pintype "input"))
    )
    (net (code "35") (name "Net-(D22-DOUT)") (class "Default")
      (node (ref "D22") (pin "2") (pinfunction "DOUT_2") (pintype "output"))
      (node (ref "D23") (pin "4") (pinfunction "DIN_4") (pintype "input"))
    )
    (net (code "36") (name "Net-(D23-DOUT)") (class "Default")
      (node (ref "D23") (pin "2") (pinfunction "DOUT_2") (pintype "output"))
      (node (ref "D24") (pin "4") (pinfunction "DIN_4") (pintype "input"))
    )
    (net (code "37") (name "Net-(D24-DOUT)") (class "Default")
      (node (ref "D24") (pin "2") (pinfunction "DOUT_2") (pintype "output"))
      (node (ref "D25") (pin "4") (pinfunction "DIN_4") (pintype "input"))
    )
    (net (code "38") (name "Net-(D25-DOUT)") (class "Default")
      (node (ref "D25") (pin "2") (pinfunction "DOUT_2") (pintype "output"))
      (node (ref "D26") (pin "4") (pinfunction "DIN_4") (pintype "input"))
    )
    (net (code "39") (name "Net-(D26-DOUT)") (class "Default")
      (node (ref "D26") (pin "2") (pinfunction "DOUT_2") (pintype "output"))
      (node (ref "D27") (pin "4") (pinfunction "DIN_4") (pintype "input"))
    )
    (net (code "40") (name "Net-(D27-DOUT)") (class "Default")
      (node (ref "D27") (pin "2") (pinfunction "DOUT_2") (pintype "output"))
      (node (ref "D28") (pin "4") (pinfunction "DIN_4") (pintype "input"))
    )
    (net (code "41") (name "Net-(D28-DOUT)") (class "Default")
      (node (ref "D28") (pin "2") (pinfunction "DOUT_2") (pintype "output"))
      (node (ref "D29") (pin "4") (pinfunction "DIN_4") (pintype "input"))
    )
    (net (code "42") (name "Net-(D29-DOUT)") (class "Default")
      (node (ref "D29") (pin "2") (pinfunction "DOUT_2") (pintype "output"))
      (node (ref "D30") (pin "4") (pinfunction "DIN_4") (pintype "input"))
    )
    (net (code "43") (name "Net-(D31-DOUT)") (class "Default")
      (node (ref "D31") (pin "2") (pinfunction "DOUT_2") (pintype "output"))
      (node (ref "D32") (pin "4") (pinfunction "DIN_4") (pintype "input"))
    )
    (net (code "44") (name "Net-(D32-DOUT)") (class "Default")
      (node (ref "D32") (pin "2") (pinfunction "DOUT_2") (pintype "output"))
      (node (ref "D33") (pin "4") (pinfunction "DIN_4") (pintype "input"))
    )
    (net (code "45") (name "Net-(D33-DOUT)") (class "Default")
      (node (ref "D33") (pin "2") (pinfunction "DOUT_2") (pintype "output"))
      (node (ref "D34") (pin "4") (pinfunction "DIN_4") (pintype "input"))
    )
    (net (code "46") (name "Net-(D34-DOUT)") (class "Default")
      (node (ref "D34") (pin "2") (pinfunction "DOUT_2") (pintype "output"))
      (node (ref "D35") (pin "4") (pinfunction "DIN_4") (pintype "input"))
    )
    (net (code "47") (name "Net-(D35-DOUT)") (class "Default")
      (node (ref "D35") (pin "2") (pinfunction "DOUT_2") (pintype "output"))
      (node (ref "D36") (pin "4") (pinfunction "DIN_4") (pintype "input"))
    )
    (net (code "48") (name "Net-(D36-DOUT)") (class "Default")
      (node (ref "D36") (pin "2") (pinfunction "DOUT_2") (pintype "output"))
      (node (ref "D37") (pin "4") (pinfunction "DIN_4") (pintype "input"))
    )
    (net (code "49") (name "Net-(D37-DOUT)") (class "Default")
      (node (ref "D37") (pin "2") (pinfunction "DOUT_2") (pintype "output"))
      (node (ref "D38") (pin "4") (pinfunction "DIN_4") (pintype "input"))
    )
    (net (code "50") (name "Net-(D38-DOUT)") (class "Default")
      (node (ref "D38") (pin "2") (pinfunction "DOUT_2") (pintype "output"))
      (node (ref "D39") (pin "4") (pinfunction "DIN_4") (pintype "input"))
    )
    (net (code "51") (name "Net-(D39-DOUT)") (class "Default")
      (node (ref "D39") (pin "2") (pinfunction "DOUT_2") (pintype "output"))
      (node (ref "D40") (pin "4") (pinfunction "DIN_4") (pintype "input"))
    )
    (net (code "52") (name "Net-(D41-DOUT)") (class "Default")
      (node (ref "D41") (pin "2") (pinfunction "DOUT_2") (pintype "output"))
      (node (ref "D42") (pin "4") (pinfunction "DIN_4") (pintype "input"))
    )
    (net (code "53") (name "Net-(D42-DOUT)") (class "Default")
      (node (ref "D42") (pin "2") (pinfunction "DOUT_2") (pintype "output"))
      (node (ref "D43") (pin "4") (pinfunction "DIN_4") (pintype "input"))
    )
    (net (code "54") (name "Net-(D43-DOUT)") (class "Default")
      (node (ref "D43") (pin "2") (pinfunction "DOUT_2") (pintype "output"))
      (node (ref "D44") (pin "4") (pinfunction "DIN_4") (pintype "input"))
    )
    (net (code "55") (name "Net-(D44-DOUT)") (class "Default")
      (node (ref "D44") (pin "2") (pinfunction "DOUT_2") (pintype "output"))
      (node (ref "D45") (pin "4") (pinfunction "DIN_4") (pintype "input"))
    )
    (net (code "56") (name "Net-(D45-DOUT)") (class "Default")
      (node (ref "D45") (pin "2") (pinfunction "DOUT_2") (pintype "output"))
      (node (ref "D46") (pin "4") (pinfunction "DIN_4") (pintype "input"))
    )
    (net (code "57") (name "Net-(D46-DOUT)") (class "Default")
      (node (ref "D46") (pin "2") (pinfunction "DOUT_2") (pintype "output"))
      (node (ref "D47") (pin "4") (pinfunction "DIN_4") (pintype "input"))
    )
    (net (code "58") (name "Net-(D47-DOUT)") (class "Default")
      (node (ref "D47") (pin "2") (pinfunction "DOUT_2") (pintype "output"))
      (node (ref "D48") (pin "4") (pinfunction "DIN_4") (pintype "input"))
    )
    (net (code "59") (name "Net-(D48-DOUT)") (class "Default")
      (node (ref "D48") (pin "2") (pinfunction "DOUT_2") (pintype "output"))
      (node (ref "D49") (pin "4") (pinfunction "DIN_4") (pintype "input"))
    )
    (net (code "60") (name "Net-(D49-DOUT)") (class "Default")
      (node (ref "D49") (pin "2") (pinfunction "DOUT_2") (pintype "output"))
      (node (ref "D50") (pin "4") (pinfunction "DIN_4") (pintype "input"))
    )
    (net (code "61") (name "Net-(D51-DOUT)") (class "Default")
      (node (ref "D51") (pin "2") (pinfunction "DOUT_2") (pintype "output"))
      (node (ref "D52") (pin "4") (pinfunction "DIN_4") (pintype "input"))
    )
    (net (code "62") (name "Net-(D52-DOUT)") (class "Default")
      (node (ref "D52") (pin "2") (pinfunction "DOUT_2") (pintype "output"))
      (node (ref "D53") (pin "4") (pinfunction "DIN_4") (pintype "input"))
    )
    (net (code "63") (name "Net-(D53-DOUT)") (class "Default")
      (node (ref "D53") (pin "2") (pinfunction "DOUT_2") (pintype "output"))
      (node (ref "D54") (pin "4") (pinfunction "DIN_4") (pintype "input"))
    )
    (net (code "64") (name "Net-(D54-DOUT)") (class "Default")
      (node (ref "D54") (pin "2") (pinfunction "DOUT_2") (pintype "output"))
      (node (ref "D55") (pin "4") (pinfunction "DIN_4") (pintype "input"))
    )
    (net (code "65") (name "Net-(D55-DOUT)") (class "Default")
      (node (ref "D55") (pin "2") (pinfunction "DOUT_2") (pintype "output"))
      (node (ref "D56") (pin "4") (pinfunction "DIN_4") (pintype "input"))
    )
    (net (code "66") (name "Net-(D56-DOUT)") (class "Default")
      (node (ref "D56") (pin "2") (pinfunction "DOUT_2") (pintype "output"))
      (node (ref "D57") (pin "4") (pinfunction "DIN_4") (pintype "input"))
    )
    (net (code "67") (name "Net-(D57-DOUT)") (class "Default")
      (node (ref "D57") (pin "2") (pinfunction "DOUT_2") (pintype "output"))
      (node (ref "D58") (pin "4") (pinfunction "DIN_4") (pintype "input"))
    )
    (net (code "68") (name "Net-(D58-DOUT)") (class "Default")
      (node (ref "D58") (pin "2") (pinfunction "DOUT_2") (pintype "output"))
      (node (ref "D59") (pin "4") (pinfunction "DIN_4") (pintype "input"))
    )
    (net (code "69") (name "Net-(D59-DOUT)") (class "Default")
      (node (ref "D59") (pin "2") (pinfunction "DOUT_2") (pintype "output"))
      (node (ref "D60") (pin "4") (pinfunction "DIN_4") (pintype "input"))
    )
    (net (code "70") (name "unconnected-(D1-DOUT-Pad2)") (class "Default")
      (node (ref "D1") (pin "2") (pinfunction "DOUT_2") (pintype "output"))
    )
  )
)
